# Timer_Autoradio_4011.net
KiCad netlist of a schematic drawn in EAGLE
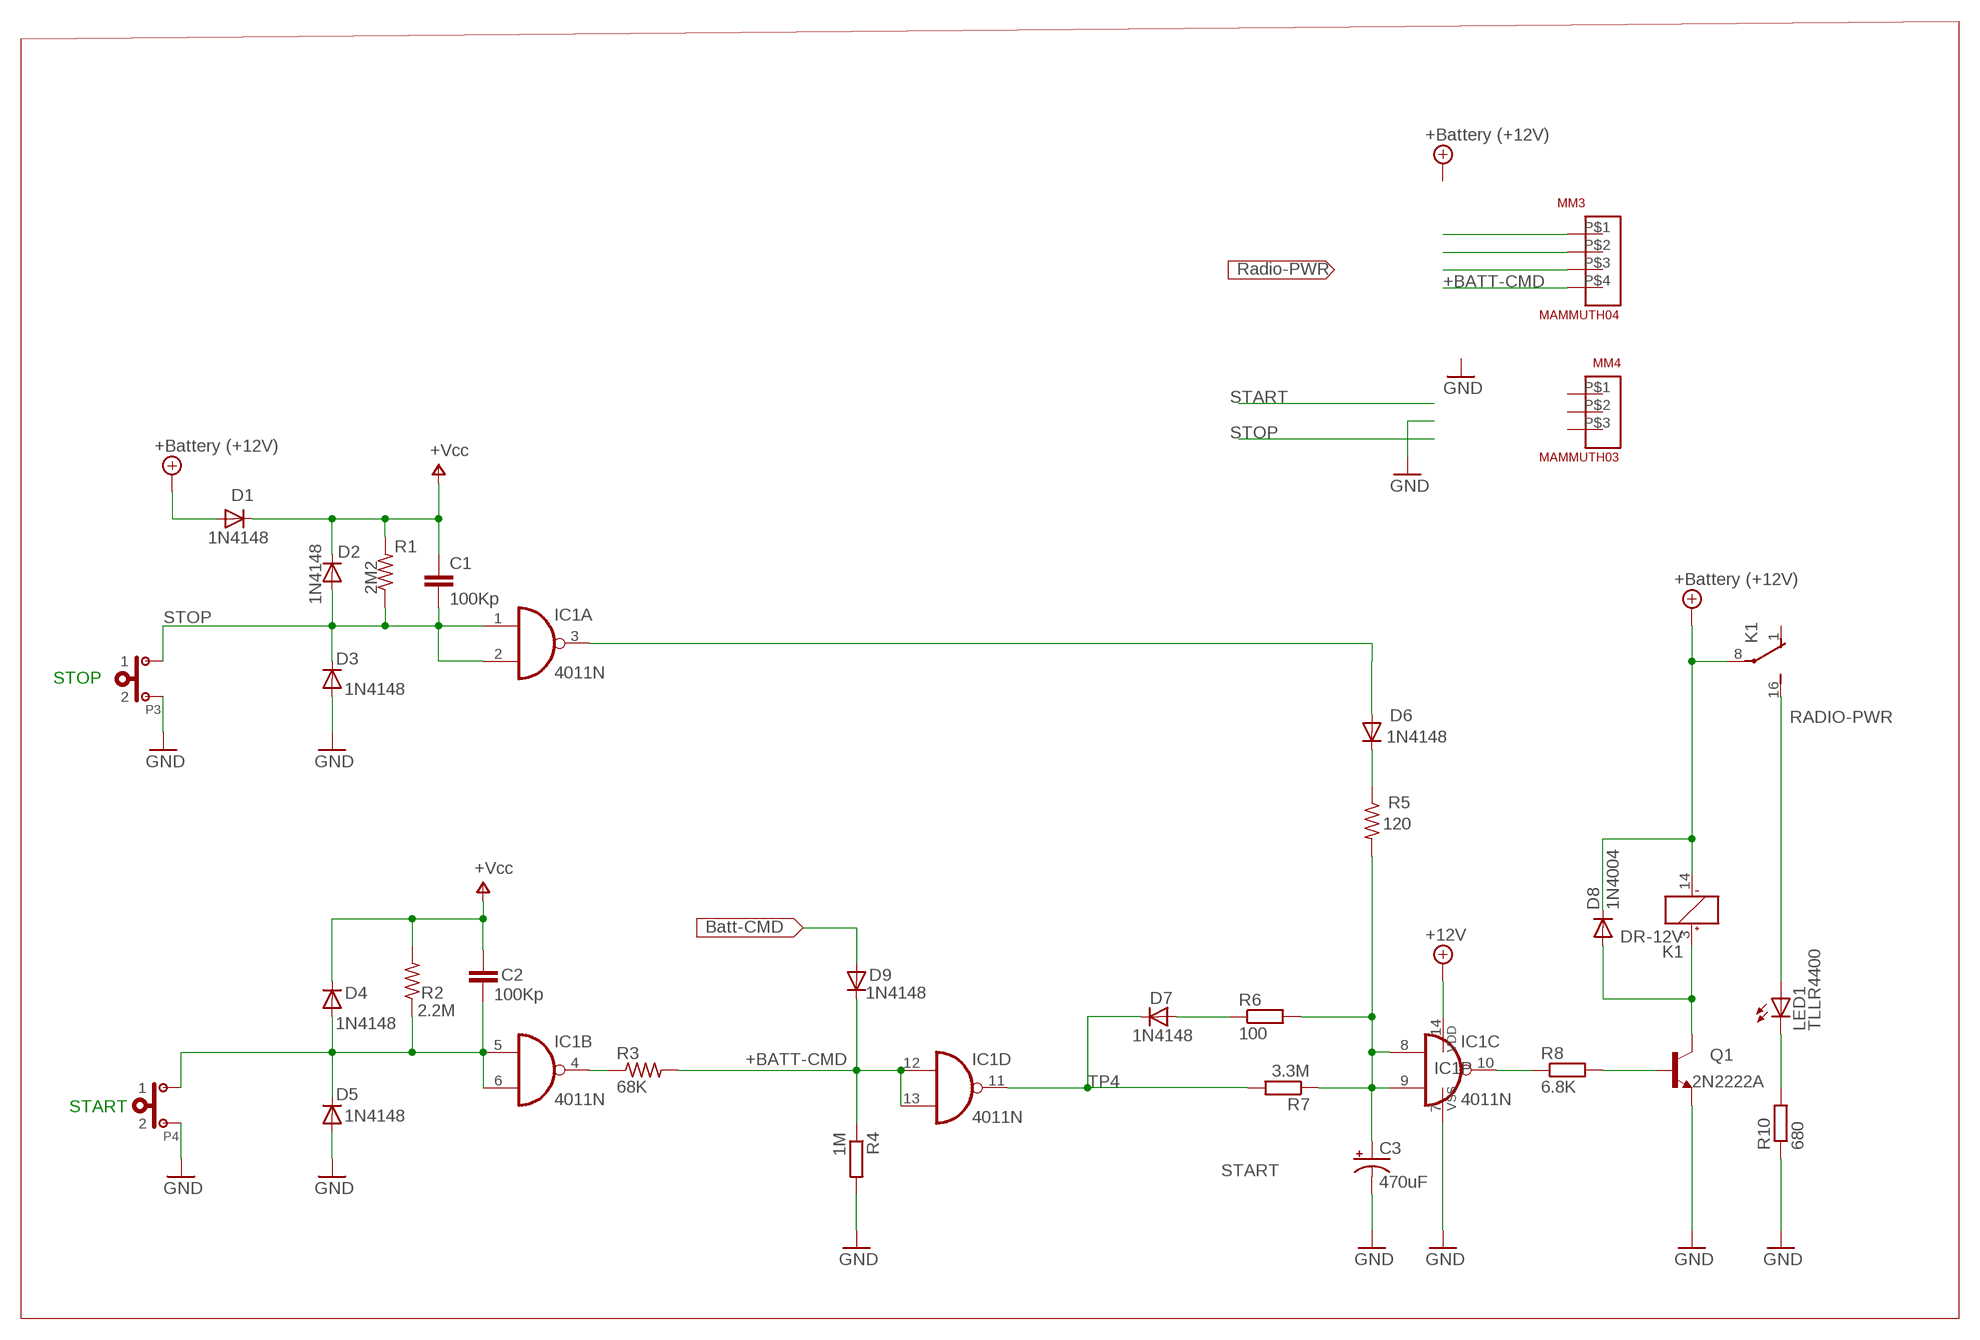
[diagram p0: schematic, sheet 1]

(export (version "E")
  (design (tool "Eeschema 10.0.6"))
  (components
    (comp (ref "C1")
      (value "100Kp")
      (footprint "eagle-import:C025-025X050")
      (libsource (lib "eagle-import") (part "C-EU025-025X050"))
    )
    (comp (ref "C2")
      (value "100Kp")
      (footprint "eagle-import:C025-025X050")
      (libsource (lib "eagle-import") (part "C-EU025-025X050"))
    )
    (comp (ref "C3")
      (value "470uF")
      (footprint "eagle-import:E3,5-8")
      (libsource (lib "eagle-import") (part "CPOL-USE3.5-8"))
    )
    (comp (ref "D1")
      (value "1N4148")
      (footprint "eagle-import:DO35-10")
      (libsource (lib "eagle-import") (part "1N4148DO35-10"))
    )
    (comp (ref "D2")
      (value "1N4148")
      (footprint "eagle-import:DO35-10")
      (libsource (lib "eagle-import") (part "1N4148DO35-10"))
    )
    (comp (ref "D3")
      (value "1N4148")
      (footprint "eagle-import:DO35-10")
      (libsource (lib "eagle-import") (part "1N4148DO35-10"))
    )
    (comp (ref "D4")
      (value "1N4148")
      (footprint "eagle-import:DO35-10")
      (libsource (lib "eagle-import") (part "1N4148DO35-10"))
    )
    (comp (ref "D5")
      (value "1N4148")
      (footprint "eagle-import:DO35-10")
      (libsource (lib "eagle-import") (part "1N4148DO35-10"))
    )
    (comp (ref "D6")
      (value "1N4148")
      (footprint "eagle-import:DO35-10")
      (libsource (lib "eagle-import") (part "1N4148DO35-10"))
    )
    (comp (ref "D7")
      (value "1N4148")
      (footprint "eagle-import:DO35-10")
      (libsource (lib "eagle-import") (part "1N4148DO35-10"))
    )
    (comp (ref "D8")
      (value "1N4004")
      (footprint "eagle-import:DO41-10")
      (libsource (lib "eagle-import") (part "1N4004"))
    )
    (comp (ref "D9")
      (value "1N4148")
      (footprint "eagle-import:DO35-10")
      (libsource (lib "eagle-import") (part "1N4148DO35-10"))
    )
    (comp (ref "IC1")
      (value "4011N")
      (footprint "eagle-import:DIL14")
      (libsource (lib "eagle-import") (part "4011N"))
    )
    (comp (ref "K1")
      (value "DR-12V")
      (footprint "eagle-import:DR-1")
      (libsource (lib "eagle-import") (part "DR-V12"))
    )
    (comp (ref "LED1")
      (value "TLLR4400")
      (footprint "eagle-import:LED3MM")
      (fields (field (name "MF") "VISHAY SEMICONDUCTOR"))
      (libsource (lib "eagle-import") (part "TLLR4400"))
    )
    (comp (ref "MM3")
      (value "MAMMUTH04")
      (footprint "eagle-import:MAMMUTH04")
      (libsource (lib "eagle-import") (part "MAMMUTH04"))
    )
    (comp (ref "MM4")
      (value "MAMMUTH03")
      (footprint "eagle-import:MAMMUTH03")
      (libsource (lib "eagle-import") (part "MAMMUTH03"))
    )
    (comp (ref "P3")
      (value "PULSANTENO")
      (footprint "eagle-import:SIP02")
      (libsource (lib "eagle-import") (part "PULSANTENO"))
    )
    (comp (ref "P4")
      (value "PULSANTENO")
      (footprint "eagle-import:SIP02")
      (libsource (lib "eagle-import") (part "PULSANTENO"))
    )
    (comp (ref "Q1")
      (value "2N2222A")
      (footprint "eagle-import:TO18")
      (libsource (lib "eagle-import") (part "2N2222A"))
    )
    (comp (ref "R1")
      (value "2M2")
      (footprint "eagle-import:0207_12")
      (libsource (lib "eagle-import") (part "R-US_0207/12"))
    )
    (comp (ref "R2")
      (value "2.2M")
      (footprint "eagle-import:0207_12")
      (libsource (lib "eagle-import") (part "R-US_0207/12"))
    )
    (comp (ref "R3")
      (value "68K")
      (footprint "eagle-import:0207_12")
      (libsource (lib "eagle-import") (part "R-US_0207/12"))
    )
    (comp (ref "R4")
      (value "1M")
      (footprint "eagle-import:0207_10")
      (libsource (lib "eagle-import") (part "R-EU_0207/10"))
    )
    (comp (ref "R5")
      (value "120")
      (footprint "eagle-import:0207_12")
      (libsource (lib "eagle-import") (part "R-US_0207/12"))
    )
    (comp (ref "R6")
      (value "100")
      (footprint "eagle-import:0207_10")
      (libsource (lib "eagle-import") (part "R-EU_0207/10"))
    )
    (comp (ref "R7")
      (value "3.3M")
      (footprint "eagle-import:0207_10")
      (libsource (lib "eagle-import") (part "R-EU_0207/10"))
    )
    (comp (ref "R8")
      (value "6.8K")
      (footprint "eagle-import:0207_10")
      (libsource (lib "eagle-import") (part "R-EU_0207/10"))
    )
    (comp (ref "R10")
      (value "680")
      (footprint "eagle-import:0207_10")
      (libsource (lib "eagle-import") (part "R-EU_0207/10"))
    )
  )
  (nets
    (net (code "1") (name "+12V") (class "Default")
      (node (ref "D1") (pin "A") (pinfunction "A_A") (pintype "passive"))
      (node (ref "D8") (pin "C") (pinfunction "C_C") (pintype "passive"))
      (node (ref "IC1") (pin "14") (pinfunction "VDD_14") (pintype "power_in"))
      (node (ref "K1") (pin "14") (pinfunction "-_14") (pintype "passive"))
      (node (ref "K1") (pin "8") (pinfunction "P_8") (pintype "passive"))
    )
    (net (code "2") (name "+Vcc") (class "Default")
      (node (ref "C1") (pin "1") (pinfunction "1_1") (pintype "passive"))
      (node (ref "C2") (pin "1") (pinfunction "1_1") (pintype "passive"))
      (node (ref "D1") (pin "C") (pinfunction "C_C") (pintype "passive"))
      (node (ref "D2") (pin "C") (pinfunction "C_C") (pintype "passive"))
      (node (ref "D4") (pin "C") (pinfunction "C_C") (pintype "passive"))
      (node (ref "R1") (pin "2") (pinfunction "2_2") (pintype "passive"))
      (node (ref "R2") (pin "2") (pinfunction "2_2") (pintype "passive"))
    )
    (net (code "3") (name "/+BATT-CMD") (class "Default")
      (node (ref "D9") (pin "C") (pinfunction "C_C") (pintype "passive"))
      (node (ref "IC1") (pin "12") (pinfunction "I0_12") (pintype "input"))
      (node (ref "IC1") (pin "13") (pinfunction "I1_13") (pintype "input"))
      (node (ref "R3") (pin "2") (pinfunction "2_2") (pintype "passive"))
      (node (ref "R4") (pin "1") (pinfunction "1_1") (pintype "passive"))
    )
    (net (code "4") (name "/RADIO-PWR") (class "Default")
      (node (ref "K1") (pin "16") (pinfunction "S_16") (pintype "passive"))
      (node (ref "LED1") (pin "A") (pinfunction "A_A") (pintype "passive"))
    )
    (net (code "5") (name "/START") (class "Default")
      (node (ref "D7") (pin "A") (pinfunction "A_A") (pintype "passive"))
      (node (ref "R6") (pin "1") (pinfunction "1_1") (pintype "passive"))
    )
    (net (code "6") (name "/STOP") (class "Default")
      (node (ref "C1") (pin "2") (pinfunction "2_2") (pintype "passive"))
      (node (ref "D2") (pin "A") (pinfunction "A_A") (pintype "passive"))
      (node (ref "D3") (pin "C") (pinfunction "C_C") (pintype "passive"))
      (node (ref "IC1") (pin "1") (pinfunction "I0_1") (pintype "input"))
      (node (ref "IC1") (pin "2") (pinfunction "I1_2") (pintype "input"))
      (node (ref "P3") (pin "1") (pinfunction "1_1") (pintype "bidirectional"))
      (node (ref "R1") (pin "1") (pinfunction "1_1") (pintype "passive"))
    )
    (net (code "7") (name "/TP4") (class "Default")
      (node (ref "D7") (pin "C") (pinfunction "C_C") (pintype "passive"))
      (node (ref "IC1") (pin "11") (pinfunction "O_11") (pintype "output"))
      (node (ref "R7") (pin "2") (pinfunction "2_2") (pintype "passive"))
    )
    (net (code "8") (name "GND") (class "Default")
      (node (ref "C3") (pin "-") (pinfunction "-_-") (pintype "passive"))
      (node (ref "D3") (pin "A") (pinfunction "A_A") (pintype "passive"))
      (node (ref "D5") (pin "A") (pinfunction "A_A") (pintype "passive"))
      (node (ref "IC1") (pin "7") (pinfunction "VSS_7") (pintype "power_in"))
      (node (ref "P3") (pin "2") (pinfunction "2_2") (pintype "bidirectional"))
      (node (ref "P4") (pin "2") (pinfunction "2_2") (pintype "bidirectional"))
      (node (ref "Q1") (pin "1") (pinfunction "E_1") (pintype "passive"))
      (node (ref "R10") (pin "1") (pinfunction "1_1") (pintype "passive"))
      (node (ref "R4") (pin "2") (pinfunction "2_2") (pintype "passive"))
    )
    (net (code "9") (name "Net-(D6-PadC)") (class "Default")
      (node (ref "D6") (pin "C") (pinfunction "C_C") (pintype "passive"))
      (node (ref "R5") (pin "1") (pinfunction "1_1") (pintype "passive"))
    )
    (net (code "10") (name "Net-(IC1A-O)") (class "Default")
      (node (ref "D6") (pin "A") (pinfunction "A_A") (pintype "passive"))
      (node (ref "IC1") (pin "3") (pinfunction "O_3") (pintype "output"))
    )
    (net (code "11") (name "Net-(IC1B-I0)") (class "Default")
      (node (ref "C2") (pin "2") (pinfunction "2_2") (pintype "passive"))
      (node (ref "D4") (pin "A") (pinfunction "A_A") (pintype "passive"))
      (node (ref "D5") (pin "C") (pinfunction "C_C") (pintype "passive"))
      (node (ref "IC1") (pin "5") (pinfunction "I0_5") (pintype "input"))
      (node (ref "IC1") (pin "6") (pinfunction "I1_6") (pintype "input"))
      (node (ref "P4") (pin "1") (pinfunction "1_1") (pintype "bidirectional"))
      (node (ref "R2") (pin "1") (pinfunction "1_1") (pintype "passive"))
    )
    (net (code "12") (name "Net-(IC1B-O)") (class "Default")
      (node (ref "IC1") (pin "4") (pinfunction "O_4") (pintype "output"))
      (node (ref "R3") (pin "1") (pinfunction "1_1") (pintype "passive"))
    )
    (net (code "13") (name "Net-(IC1C-I0)") (class "Default")
      (node (ref "C3") (pin "+") (pinfunction "+_+") (pintype "passive"))
      (node (ref "IC1") (pin "8") (pinfunction "I0_8") (pintype "input"))
      (node (ref "IC1") (pin "9") (pinfunction "I1_9") (pintype "input"))
      (node (ref "R5") (pin "2") (pinfunction "2_2") (pintype "passive"))
      (node (ref "R6") (pin "2") (pinfunction "2_2") (pintype "passive"))
      (node (ref "R7") (pin "1") (pinfunction "1_1") (pintype "passive"))
    )
    (net (code "14") (name "Net-(IC1C-O)") (class "Default")
      (node (ref "IC1") (pin "10") (pinfunction "O_10") (pintype "output"))
      (node (ref "R8") (pin "1") (pinfunction "1_1") (pintype "passive"))
    )
    (net (code "15") (name "Net-(K1A-+)") (class "Default")
      (node (ref "D8") (pin "A") (pinfunction "A_A") (pintype "passive"))
      (node (ref "K1") (pin "3") (pinfunction "+_3") (pintype "passive"))
      (node (ref "Q1") (pin "3") (pinfunction "C_3") (pintype "passive"))
    )
    (net (code "16") (name "Net-(LED1-C)") (class "Default")
      (node (ref "LED1") (pin "K") (pinfunction "C_K") (pintype "passive"))
      (node (ref "R10") (pin "2") (pinfunction "2_2") (pintype "passive"))
    )
    (net (code "17") (name "Net-(Q1-B)") (class "Default")
      (node (ref "Q1") (pin "2") (pinfunction "B_2") (pintype "passive"))
      (node (ref "R8") (pin "2") (pinfunction "2_2") (pintype "passive"))
    )
    (net (code "18") (name "unconnected-(D9-PadA)") (class "Default")
      (node (ref "D9") (pin "A") (pinfunction "A_A") (pintype "passive"))
    )
    (net (code "19") (name "unconnected-(K1B-O-Pad1)") (class "Default")
      (node (ref "K1") (pin "1") (pinfunction "O_1") (pintype "passive"))
    )
    (net (code "20") (name "unconnected-(MM3-PadP$1)") (class "Default")
      (node (ref "MM3") (pin "P$1") (pinfunction "P$1_P$1") (pintype "bidirectional"))
    )
    (net (code "21") (name "unconnected-(MM3-PadP$2)") (class "Default")
      (node (ref "MM3") (pin "P$2") (pinfunction "P$2_P$2") (pintype "bidirectional"))
    )
    (net (code "22") (name "unconnected-(MM3-PadP$3)") (class "Default")
      (node (ref "MM3") (pin "P$3") (pinfunction "P$3_P$3") (pintype "bidirectional"))
    )
    (net (code "23") (name "unconnected-(MM3-PadP$4)") (class "Default")
      (node (ref "MM3") (pin "P$4") (pinfunction "P$4_P$4") (pintype "bidirectional"))
    )
    (net (code "24") (name "unconnected-(MM4-PadP$1)") (class "Default")
      (node (ref "MM4") (pin "P$1") (pinfunction "P$1_P$1") (pintype "bidirectional"))
    )
    (net (code "25") (name "unconnected-(MM4-PadP$2)") (class "Default")
      (node (ref "MM4") (pin "P$2") (pinfunction "P$2_P$2") (pintype "bidirectional"))
    )
    (net (code "26") (name "unconnected-(MM4-PadP$3)") (class "Default")
      (node (ref "MM4") (pin "P$3") (pinfunction "P$3_P$3") (pintype "bidirectional"))
    )
  )
)
